# Attenuator_Proto.net
KiCad netlist of a schematic drawn in Altium Designer
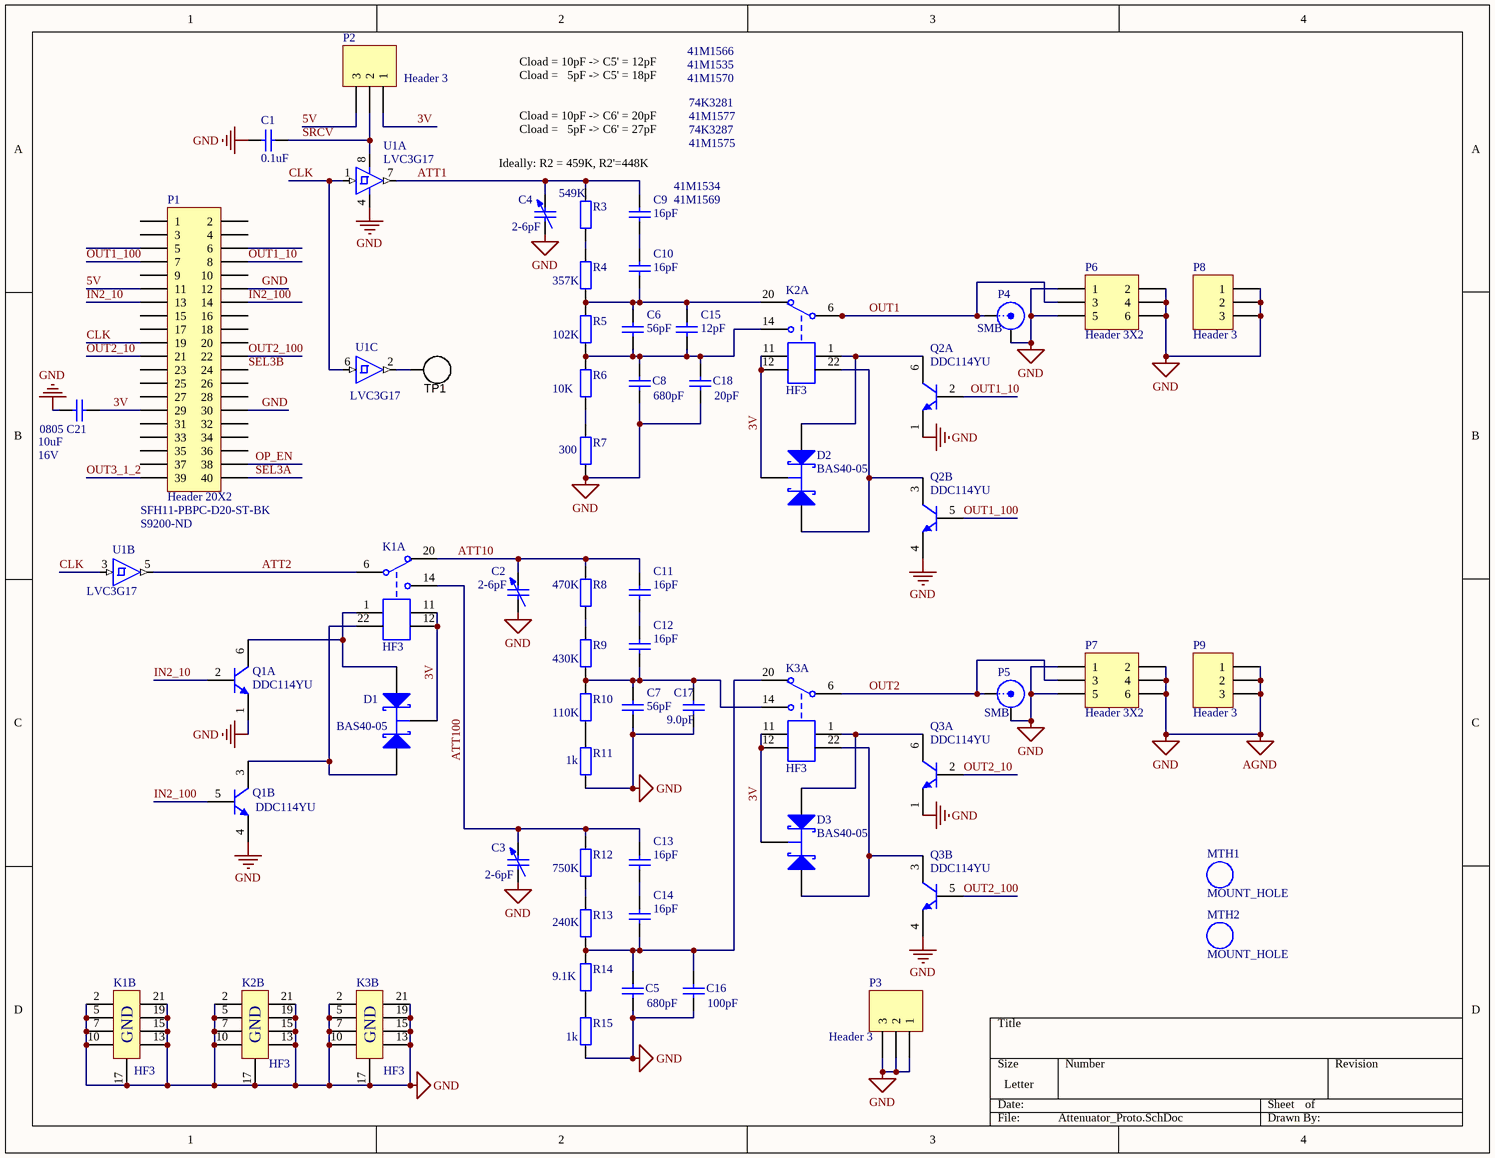
[diagram p0: Attenuator_Proto.SchDoc]

(export (version "E")
  (design (tool "Eeschema 10.0.6"))
  (components
    (comp (ref "C1")
      (value "0.1uF")
      (footprint "C0805")
      (description "Capacitor")
      (fields (field (name "Comment") "Cap") (field (name "PUBLISHER") "Altium Limited"))
      (libsource (lib "Miscellaneous Devices") (part "Cap"))
    )
    (comp (ref "C2")
      (value "2-6pF")
      (footprint "CAPC3225N")
      (description "Variable or Adjustable Capacitor")
      (fields (field (name "Comment") "Cap Var") (field (name "PUBLISHER") "Altium Limited"))
      (libsource (lib "Miscellaneous Devices") (part "Cap Var"))
    )
    (comp (ref "C3")
      (value "2-6pF")
      (footprint "CAPC3225N")
      (description "Variable or Adjustable Capacitor")
      (fields (field (name "Comment") "Cap Var") (field (name "PUBLISHER") "Altium Limited"))
      (libsource (lib "Miscellaneous Devices") (part "Cap Var"))
    )
    (comp (ref "C4")
      (value "2-6pF")
      (footprint "CAPC3225N")
      (description "Variable or Adjustable Capacitor")
      (fields (field (name "Comment") "Cap Var") (field (name "PUBLISHER") "Altium Limited"))
      (libsource (lib "Miscellaneous Devices") (part "Cap Var"))
    )
    (comp (ref "C5")
      (value "680pF")
      (footprint "c0805")
      (description "Capacitor")
      (fields (field (name "Comment") "Cap") (field (name "PUBLISHER") "Altium Limited"))
      (libsource (lib "Miscellaneous Devices") (part "Cap"))
    )
    (comp (ref "C6")
      (value "56pF")
      (footprint "c0805")
      (description "Capacitor")
      (fields (field (name "Comment") "Cap") (field (name "PUBLISHER") "Altium Limited"))
      (libsource (lib "Miscellaneous Devices") (part "Cap"))
    )
    (comp (ref "C7")
      (value "56pF")
      (footprint "c0805")
      (description "Capacitor")
      (fields (field (name "Comment") "Cap") (field (name "PUBLISHER") "Altium Limited"))
      (libsource (lib "Miscellaneous Devices") (part "Cap"))
    )
    (comp (ref "C8")
      (value "680pF")
      (footprint "c0805")
      (description "Capacitor")
      (fields (field (name "Comment") "Cap") (field (name "PUBLISHER") "Altium Limited"))
      (libsource (lib "Miscellaneous Devices") (part "Cap"))
    )
    (comp (ref "C9")
      (value "16pF")
      (footprint "c0805")
      (description "Capacitor")
      (fields
        (field (name "SUPPLIER PART NUMBER 1") "41M1569")
        (field (name "SUPPLIER PART NUMBER 2") "41M1534")
        (field (name "Comment") "Cap")
        (field (name "PUBLISHER") "Altium Limited")
      )
      (libsource (lib "Miscellaneous Devices") (part "Cap"))
    )
    (comp (ref "C10")
      (value "16pF")
      (footprint "c0805")
      (description "Capacitor")
      (fields (field (name "Comment") "Cap") (field (name "PUBLISHER") "Altium Limited"))
      (libsource (lib "Miscellaneous Devices") (part "Cap"))
    )
    (comp (ref "C11")
      (value "16pF")
      (footprint "c0805")
      (description "Capacitor")
      (fields (field (name "Comment") "Cap") (field (name "PUBLISHER") "Altium Limited"))
      (libsource (lib "Miscellaneous Devices") (part "Cap"))
    )
    (comp (ref "C12")
      (value "16pF")
      (footprint "c0805")
      (description "Capacitor")
      (fields (field (name "Comment") "Cap") (field (name "PUBLISHER") "Altium Limited"))
      (libsource (lib "Miscellaneous Devices") (part "Cap"))
    )
    (comp (ref "C13")
      (value "16pF")
      (footprint "c0805")
      (description "Capacitor")
      (fields (field (name "Comment") "Cap") (field (name "PUBLISHER") "Altium Limited"))
      (libsource (lib "Miscellaneous Devices") (part "Cap"))
    )
    (comp (ref "C14")
      (value "16pF")
      (footprint "c0805")
      (description "Capacitor")
      (fields (field (name "Comment") "Cap") (field (name "PUBLISHER") "Altium Limited"))
      (libsource (lib "Miscellaneous Devices") (part "Cap"))
    )
    (comp (ref "C15")
      (value "12pF")
      (footprint "c0805")
      (description "Capacitor")
      (fields
        (field (name "SUPPLIER PART NUMBER 2") "41M1570")
        (field (name "SUPPLIER PART NUMBER 1") "41M1535")
        (field (name "SUPPLIER PART NUMBER 3") "41M1566")
        (field (name "Comment") "Cap")
        (field (name "PUBLISHER") "Altium Limited")
      )
      (libsource (lib "Miscellaneous Devices") (part "Cap"))
    )
    (comp (ref "C16")
      (value "100pF")
      (footprint "c0805")
      (description "Capacitor")
      (fields (field (name "Comment") "Cap") (field (name "PUBLISHER") "Altium Limited"))
      (libsource (lib "Miscellaneous Devices") (part "Cap"))
    )
    (comp (ref "C17")
      (value "9.0pF")
      (footprint "c0805")
      (description "Capacitor")
      (fields (field (name "Comment") "Cap") (field (name "PUBLISHER") "Altium Limited"))
      (libsource (lib "Miscellaneous Devices") (part "Cap"))
    )
    (comp (ref "C18")
      (value "20pF")
      (footprint "c0805")
      (description "Capacitor")
      (fields
        (field (name "SUPPLIER PART NUMBER 1") "41M1575")
        (field (name "SUPPLIER PART NUMBER 2") "74K3287")
        (field (name "SUPPLIER PART NUMBER 3") "41M1577")
        (field (name "SUPPLIER PART NUMBER 4") "74K3281")
        (field (name "Comment") "Cap")
        (field (name "PUBLISHER") "Altium Limited")
      )
      (libsource (lib "Miscellaneous Devices") (part "Cap"))
    )
    (comp (ref "C21")
      (value "10uF")
      (footprint "CAPC2512L")
      (description "Capacitor (Semiconductor SIM Model)")
      (fields
        (field (name "PACKAGEREFERENCE") "0805")
        (field (name "VOLTAGE") "16V")
        (field (name "MANUFACTURER") "Murata")
        (field (name "PARTNUMBER") "GRM21BF51C106ZE15L")
        (field (name "PUBLISHER") "Altium Limited")
      )
      (libsource (lib "Miscellaneous Devices") (part "Cap Semi"))
    )
    (comp (ref "D1")
      (value "BAS40-05")
      (footprint "SOT-23")
      (description "Silicon AF Schottky Diode for High-Speed Switching")
      (fields (field (name "PUBLISHER") "Altium Limited"))
      (libsource (lib "Infineon Discrete Diode") (part "BAS40-05"))
    )
    (comp (ref "D2")
      (value "BAS40-05")
      (footprint "SOT-23")
      (description "Silicon AF Schottky Diode for High-Speed Switching")
      (fields (field (name "PUBLISHER") "Altium Limited"))
      (libsource (lib "Infineon Discrete Diode") (part "BAS40-05"))
    )
    (comp (ref "D3")
      (value "BAS40-05")
      (footprint "SOT-23")
      (description "Silicon AF Schottky Diode for High-Speed Switching")
      (fields (field (name "PUBLISHER") "Altium Limited"))
      (libsource (lib "Infineon Discrete Diode") (part "BAS40-05"))
    )
    (comp (ref "K1")
      (value "HF3_2coils_latching")
      (footprint "HF3-75_Ohm")
      (description "HF3 Relay, Latching type, 2 coils")
      (fields (field (name "MANUFACTURER") "Tyco Electronics") (field (name "PARTNUMBER") "HF3"))
      (libsource (lib "Chudik") (part "HF3_2coils_latching"))
    )
    (comp (ref "K2")
      (value "HF3_2coils_latching")
      (footprint "HF3-75_Ohm")
      (description "HF3 Relay, Latching type, 2 coils")
      (fields (field (name "MANUFACTURER") "Tyco Electronics") (field (name "PARTNUMBER") "HF3"))
      (libsource (lib "Chudik") (part "HF3_2coils_latching"))
    )
    (comp (ref "K3")
      (value "HF3_2coils_latching")
      (footprint "HF3-75_Ohm")
      (description "HF3 Relay, Latching type, 2 coils")
      (fields (field (name "MANUFACTURER") "Tyco Electronics") (field (name "PARTNUMBER") "HF3"))
      (libsource (lib "") (part "HF3_2coils_latching_1"))
    )
    (comp (ref "MTH1")
      (value "MOUNT_HOLE")
      (footprint "MTHOLE_UEG_EU_BE")
      (libsource (lib "CONTROLLER_BOARD") (part "MOUNT_HOLE"))
    )
    (comp (ref "MTH2")
      (value "MOUNT_HOLE")
      (footprint "MTHOLE_UEG_EU_BE")
      (libsource (lib "CONTROLLER_BOARD") (part "MOUNT_HOLE"))
    )
    (comp (ref "P1")
      (value "Header 20X2")
      (footprint "HDR2X20")
      (description "Header, 20-Pin, Dual row")
      (fields
        (field (name "PARTNUMBER") "SFH11-PBPC-D20-ST-BK")
        (field (name "SUPPLIER PART NUMBER 1") "S9200-ND")
        (field (name "PUBLISHER") "Altium Limited")
      )
      (libsource (lib "Miscellaneous Connectors") (part "Header 20X2"))
    )
    (comp (ref "P2")
      (value "Header 3")
      (footprint "HDR1X3")
      (description "Header, 3-Pin")
      (fields (field (name "PUBLISHER") "Altium Limited"))
      (libsource (lib "") (part "Header 3_1"))
    )
    (comp (ref "P3")
      (value "Header 3")
      (footprint "HDR1X3")
      (description "Header, 3-Pin")
      (fields (field (name "PUBLISHER") "Altium Limited"))
      (libsource (lib "") (part "Header 3_2"))
    )
    (comp (ref "P4")
      (value "SMB")
      (footprint "SMB_V-RJ45")
      (description "SMB Straight Connector")
      (fields (field (name "PUBLISHER") "Altium Limited"))
      (libsource (lib "Miscellaneous Connectors") (part "SMB"))
    )
    (comp (ref "P5")
      (value "SMB")
      (footprint "SMB_V-RJ45")
      (description "SMB Straight Connector")
      (fields (field (name "PUBLISHER") "Altium Limited"))
      (libsource (lib "Miscellaneous Connectors") (part "SMB"))
    )
    (comp (ref "P6")
      (value "Header 3X2")
      (footprint "HDR2X3")
      (description "Header, 3-Pin, Dual row")
      (fields (field (name "PUBLISHER") "Altium Limited"))
      (libsource (lib "Miscellaneous Connectors") (part "Header 3X2"))
    )
    (comp (ref "P7")
      (value "Header 3X2")
      (footprint "HDR2X3")
      (description "Header, 3-Pin, Dual row")
      (fields (field (name "PUBLISHER") "Altium Limited"))
      (libsource (lib "Miscellaneous Connectors") (part "Header 3X2"))
    )
    (comp (ref "P8")
      (value "Header 3")
      (footprint "HDR1X3")
      (description "Header, 3-Pin")
      (fields (field (name "PUBLISHER") "Altium Limited"))
      (libsource (lib "Miscellaneous Connectors") (part "Header 3"))
    )
    (comp (ref "P9")
      (value "Header 3")
      (footprint "HDR1X3")
      (description "Header, 3-Pin")
      (fields (field (name "PUBLISHER") "Altium Limited"))
      (libsource (lib "Miscellaneous Connectors") (part "Header 3"))
    )
    (comp (ref "Q1")
      (value "DDCxxxxU")
      (footprint "SOT-363")
      (description "NPN PRE-BIASED SMALL SIGNAL DUAL SURFACE MOUNT TRANSISTOR")
      (fields (field (name "PARTNUMBER") "DDC114YU"))
      (libsource (lib "iXBT") (part "DDCxxxxU"))
    )
    (comp (ref "Q2")
      (value "DDCxxxxU")
      (footprint "SOT-363")
      (description "NPN PRE-BIASED SMALL SIGNAL DUAL SURFACE MOUNT TRANSISTOR")
      (fields (field (name "PARTNUMBER") "DDC114YU"))
      (libsource (lib "iXBT") (part "DDCxxxxU"))
    )
    (comp (ref "Q3")
      (value "DDCxxxxU")
      (footprint "SOT-363")
      (description "NPN PRE-BIASED SMALL SIGNAL DUAL SURFACE MOUNT TRANSISTOR")
      (fields (field (name "PARTNUMBER") "DDC114YU"))
      (libsource (lib "iXBT") (part "DDCxxxxU"))
    )
    (comp (ref "R3")
      (value "549K")
      (footprint "0805")
      (description "Resistor")
      (fields (field (name "Comment") "Res2") (field (name "PUBLISHER") "Altium Limited"))
      (libsource (lib "Miscellaneous Devices") (part "Res2"))
    )
    (comp (ref "R4")
      (value "357K")
      (footprint "0805")
      (description "Resistor")
      (fields (field (name "Comment") "Res2") (field (name "PUBLISHER") "Altium Limited"))
      (libsource (lib "Miscellaneous Devices") (part "Res2"))
    )
    (comp (ref "R5")
      (value "102K")
      (footprint "0805")
      (description "Resistor")
      (fields (field (name "Comment") "Res2") (field (name "PUBLISHER") "Altium Limited"))
      (libsource (lib "Miscellaneous Devices") (part "Res2"))
    )
    (comp (ref "R6")
      (value "10K")
      (footprint "0805")
      (description "Resistor")
      (fields (field (name "Comment") "Res2") (field (name "PUBLISHER") "Altium Limited"))
      (libsource (lib "Miscellaneous Devices") (part "Res2"))
    )
    (comp (ref "R7")
      (value "300")
      (footprint "0805")
      (description "Resistor")
      (fields (field (name "Comment") "Res2") (field (name "PUBLISHER") "Altium Limited"))
      (libsource (lib "Miscellaneous Devices") (part "Res2"))
    )
    (comp (ref "R8")
      (value "470K")
      (footprint "0805")
      (description "Resistor")
      (fields (field (name "Comment") "Res2") (field (name "PUBLISHER") "Altium Limited"))
      (libsource (lib "Miscellaneous Devices") (part "Res2"))
    )
    (comp (ref "R9")
      (value "430K")
      (footprint "0805")
      (description "Resistor")
      (fields (field (name "Comment") "Res2") (field (name "PUBLISHER") "Altium Limited"))
      (libsource (lib "Miscellaneous Devices") (part "Res2"))
    )
    (comp (ref "R10")
      (value "110K")
      (footprint "0805")
      (description "Resistor")
      (fields (field (name "Comment") "Res2") (field (name "PUBLISHER") "Altium Limited"))
      (libsource (lib "Miscellaneous Devices") (part "Res2"))
    )
    (comp (ref "R11")
      (value "1k")
      (footprint "0805")
      (description "Resistor")
      (fields (field (name "Comment") "Res2") (field (name "PUBLISHER") "Altium Limited"))
      (libsource (lib "Miscellaneous Devices") (part "Res2"))
    )
    (comp (ref "R12")
      (value "750K")
      (footprint "0805")
      (description "Resistor")
      (fields (field (name "Comment") "Res2") (field (name "PUBLISHER") "Altium Limited"))
      (libsource (lib "Miscellaneous Devices") (part "Res2"))
    )
    (comp (ref "R13")
      (value "240K")
      (footprint "0805")
      (description "Resistor")
      (fields (field (name "Comment") "Res2") (field (name "PUBLISHER") "Altium Limited"))
      (libsource (lib "Miscellaneous Devices") (part "Res2"))
    )
    (comp (ref "R14")
      (value "9.1K")
      (footprint "0805")
      (description "Resistor")
      (fields (field (name "Comment") "Res2") (field (name "PUBLISHER") "Altium Limited"))
      (libsource (lib "Miscellaneous Devices") (part "Res2"))
    )
    (comp (ref "R15")
      (value "1k")
      (footprint "0805")
      (description "Resistor")
      (fields (field (name "Comment") "Res2") (field (name "PUBLISHER") "Altium Limited"))
      (libsource (lib "Miscellaneous Devices") (part "Res2"))
    )
    (comp (ref "TP1")
      (value "TESTPOINT")
      (footprint "TESTPOINT")
      (description "TEST POINT.  No entry in BOM.")
      (libsource (lib "NSC MiscParts") (part "TESTPOINT"))
    )
    (comp (ref "U1")
      (value "LVC3G17")
      (footprint "sm8")
      (fields
        (field (name "MANUFACTURER") "Texas Instruments")
        (field (name "MANUFACTURER PART NUMBER") "SN74LVC3G17DCTR")
      )
      (libsource (lib "VIVENG_Library") (part "SN74LVC3G17DCTR"))
    )
  )
  (nets
    (net (code "1") (name "/3V") (class "Default")
      (node (ref "C21") (pin "1") (pinfunction "1_1") (pintype "passive"))
      (node (ref "D1") (pin "3") (pinfunction "K_3") (pintype "passive"))
      (node (ref "D2") (pin "3") (pinfunction "K_3") (pintype "passive"))
      (node (ref "D3") (pin "3") (pinfunction "K_3") (pintype "passive"))
      (node (ref "K1") (pin "11") (pinfunction "11_11") (pintype "passive"))
      (node (ref "K1") (pin "12") (pinfunction "12_12") (pintype "passive"))
      (node (ref "K2") (pin "11") (pinfunction "11_11") (pintype "passive"))
      (node (ref "K2") (pin "12") (pinfunction "12_12") (pintype "passive"))
      (node (ref "K3") (pin "11") (pinfunction "11_11") (pintype "passive"))
      (node (ref "K3") (pin "12") (pinfunction "12_12") (pintype "passive"))
      (node (ref "P1") (pin "29") (pinfunction "29_29") (pintype "passive"))
      (node (ref "P2") (pin "1") (pinfunction "1_1") (pintype "passive"))
    )
    (net (code "2") (name "/5V") (class "Default")
      (node (ref "P1") (pin "11") (pinfunction "11_11") (pintype "passive"))
      (node (ref "P2") (pin "3") (pinfunction "3_3") (pintype "passive"))
    )
    (net (code "3") (name "/ATT1") (class "Default")
      (node (ref "C4") (pin "2") (pinfunction "2_2") (pintype "passive"))
      (node (ref "C9") (pin "2") (pinfunction "2_2") (pintype "passive"))
      (node (ref "R3") (pin "2") (pinfunction "2_2") (pintype "passive"))
      (node (ref "U1") (pin "7") (pinfunction "1Y_7") (pintype "output"))
    )
    (net (code "4") (name "/ATT2") (class "Default")
      (node (ref "K1") (pin "6") (pinfunction "6_6") (pintype "passive"))
      (node (ref "U1") (pin "5") (pinfunction "2Y_5") (pintype "output"))
    )
    (net (code "5") (name "/ATT10") (class "Default")
      (node (ref "C11") (pin "2") (pinfunction "2_2") (pintype "passive"))
      (node (ref "C2") (pin "2") (pinfunction "2_2") (pintype "passive"))
      (node (ref "K1") (pin "20") (pinfunction "20_20") (pintype "passive"))
      (node (ref "R8") (pin "2") (pinfunction "2_2") (pintype "passive"))
    )
    (net (code "6") (name "/ATT100") (class "Default")
      (node (ref "C13") (pin "2") (pinfunction "2_2") (pintype "passive"))
      (node (ref "C3") (pin "2") (pinfunction "2_2") (pintype "passive"))
      (node (ref "K1") (pin "14") (pinfunction "14_14") (pintype "passive"))
      (node (ref "R12") (pin "2") (pinfunction "2_2") (pintype "passive"))
    )
    (net (code "7") (name "/CLK") (class "Default")
      (node (ref "P1") (pin "19") (pinfunction "19_19") (pintype "passive"))
      (node (ref "U1") (pin "1") (pinfunction "1A_1") (pintype "input"))
      (node (ref "U1") (pin "3") (pinfunction "2A_3") (pintype "input"))
      (node (ref "U1") (pin "6") (pinfunction "3A_6") (pintype "input"))
    )
    (net (code "8") (name "/IN2_10") (class "Default")
      (node (ref "P1") (pin "13") (pinfunction "13_13") (pintype "passive"))
      (node (ref "Q1") (pin "2") (pinfunction "B_2") (pintype "passive"))
    )
    (net (code "9") (name "/IN2_100") (class "Default")
      (node (ref "P1") (pin "14") (pinfunction "14_14") (pintype "passive"))
      (node (ref "Q1") (pin "5") (pinfunction "B_5") (pintype "passive"))
    )
    (net (code "10") (name "/OP_EN") (class "Default")
      (node (ref "P1") (pin "38") (pinfunction "38_38") (pintype "passive"))
    )
    (net (code "11") (name "/OUT1") (class "Default")
      (node (ref "K2") (pin "6") (pinfunction "6_6") (pintype "passive"))
      (node (ref "P4") (pin "1") (pinfunction "X_1") (pintype "passive"))
      (node (ref "P6") (pin "3") (pinfunction "3_3") (pintype "passive"))
    )
    (net (code "12") (name "/OUT1_10") (class "Default")
      (node (ref "P1") (pin "8") (pinfunction "8_8") (pintype "passive"))
      (node (ref "Q2") (pin "2") (pinfunction "B_2") (pintype "passive"))
    )
    (net (code "13") (name "/OUT1_100") (class "Default")
      (node (ref "P1") (pin "7") (pinfunction "7_7") (pintype "passive"))
      (node (ref "Q2") (pin "5") (pinfunction "B_5") (pintype "passive"))
    )
    (net (code "14") (name "/OUT2") (class "Default")
      (node (ref "K3") (pin "6") (pinfunction "6_6") (pintype "passive"))
      (node (ref "P5") (pin "1") (pinfunction "X_1") (pintype "passive"))
      (node (ref "P7") (pin "3") (pinfunction "3_3") (pintype "passive"))
    )
    (net (code "15") (name "/OUT2_10") (class "Default")
      (node (ref "P1") (pin "21") (pinfunction "21_21") (pintype "passive"))
      (node (ref "Q3") (pin "2") (pinfunction "B_2") (pintype "passive"))
    )
    (net (code "16") (name "/OUT2_100") (class "Default")
      (node (ref "P1") (pin "22") (pinfunction "22_22") (pintype "passive"))
      (node (ref "Q3") (pin "5") (pinfunction "B_5") (pintype "passive"))
    )
    (net (code "17") (name "/OUT3_1_2") (class "Default")
      (node (ref "P1") (pin "39") (pinfunction "39_39") (pintype "passive"))
    )
    (net (code "18") (name "/SEL3A") (class "Default")
      (node (ref "P1") (pin "40") (pinfunction "40_40") (pintype "passive"))
    )
    (net (code "19") (name "/SEL3B") (class "Default")
      (node (ref "P1") (pin "24") (pinfunction "24_24") (pintype "passive"))
    )
    (net (code "20") (name "/SRCV") (class "Default")
      (node (ref "C1") (pin "1") (pinfunction "1_1") (pintype "passive"))
      (node (ref "P2") (pin "2") (pinfunction "2_2") (pintype "passive"))
      (node (ref "U1") (pin "8") (pinfunction "VCC_8") (pintype "power_in"))
    )
    (net (code "21") (name "AGND") (class "Default")
      (node (ref "C1") (pin "2") (pinfunction "2_2") (pintype "passive"))
      (node (ref "C16") (pin "1") (pinfunction "1_1") (pintype "passive"))
      (node (ref "C17") (pin "1") (pinfunction "1_1") (pintype "passive"))
      (node (ref "C18") (pin "1") (pinfunction "1_1") (pintype "passive"))
      (node (ref "C2") (pin "1") (pinfunction "1_1") (pintype "passive"))
      (node (ref "C21") (pin "2") (pinfunction "2_2") (pintype "passive"))
      (node (ref "C3") (pin "1") (pinfunction "1_1") (pintype "passive"))
      (node (ref "C4") (pin "1") (pinfunction "1_1") (pintype "passive"))
      (node (ref "C5") (pin "1") (pinfunction "1_1") (pintype "passive"))
      (node (ref "C7") (pin "1") (pinfunction "1_1") (pintype "passive"))
      (node (ref "C8") (pin "1") (pinfunction "1_1") (pintype "passive"))
      (node (ref "K1") (pin "10") (pinfunction "GND_10") (pintype "power_in"))
      (node (ref "K1") (pin "13") (pinfunction "GND_13") (pintype "power_in"))
      (node (ref "K1") (pin "15") (pinfunction "GND_15") (pintype "power_in"))
      (node (ref "K1") (pin "17") (pinfunction "GND_17") (pintype "power_in"))
      (node (ref "K1") (pin "19") (pinfunction "GND_19") (pintype "power_in"))
      (node (ref "K1") (pin "2") (pinfunction "GND_2") (pintype "power_in"))
      (node (ref "K1") (pin "21") (pinfunction "GND_21") (pintype "power_in"))
      (node (ref "K1") (pin "5") (pinfunction "GND_5") (pintype "power_in"))
      (node (ref "K1") (pin "7") (pinfunction "GND_7") (pintype "power_in"))
      (node (ref "K2") (pin "10") (pinfunction "GND_10") (pintype "power_in"))
      (node (ref "K2") (pin "13") (pinfunction "GND_13") (pintype "power_in"))
      (node (ref "K2") (pin "15") (pinfunction "GND_15") (pintype "power_in"))
      (node (ref "K2") (pin "17") (pinfunction "GND_17") (pintype "power_in"))
      (node (ref "K2") (pin "19") (pinfunction "GND_19") (pintype "power_in"))
      (node (ref "K2") (pin "2") (pinfunction "GND_2") (pintype "power_in"))
      (node (ref "K2") (pin "21") (pinfunction "GND_21") (pintype "power_in"))
      (node (ref "K2") (pin "5") (pinfunction "GND_5") (pintype "power_in"))
      (node (ref "K2") (pin "7") (pinfunction "GND_7") (pintype "power_in"))
      (node (ref "K3") (pin "10") (pinfunction "GND_10") (pintype "power_in"))
      (node (ref "K3") (pin "13") (pinfunction "GND_13") (pintype "power_in"))
      (node (ref "K3") (pin "15") (pinfunction "GND_15") (pintype "power_in"))
      (node (ref "K3") (pin "17") (pinfunction "GND_17") (pintype "power_in"))
      (node (ref "K3") (pin "19") (pinfunction "GND_19") (pintype "power_in"))
      (node (ref "K3") (pin "2") (pinfunction "GND_2") (pintype "power_in"))
      (node (ref "K3") (pin "21") (pinfunction "GND_21") (pintype "power_in"))
      (node (ref "K3") (pin "5") (pinfunction "GND_5") (pintype "power_in"))
      (node (ref "K3") (pin "7") (pinfunction "GND_7") (pintype "power_in"))
      (node (ref "P1") (pin "12") (pinfunction "12_12") (pintype "passive"))
      (node (ref "P1") (pin "30") (pinfunction "30_30") (pintype "passive"))
      (node (ref "P3") (pin "1") (pinfunction "1_1") (pintype "passive"))
      (node (ref "P3") (pin "2") (pinfunction "2_2") (pintype "passive"))
      (node (ref "P3") (pin "3") (pinfunction "3_3") (pintype "passive"))
      (node (ref "P4") (pin "2") (pinfunction "Y_2") (pintype "passive"))
      (node (ref "P5") (pin "2") (pinfunction "Y_2") (pintype "passive"))
      (node (ref "P6") (pin "1") (pinfunction "1_1") (pintype "passive"))
      (node (ref "P6") (pin "2") (pinfunction "2_2") (pintype "passive"))
      (node (ref "P6") (pin "4") (pinfunction "4_4") (pintype "passive"))
      (node (ref "P6") (pin "5") (pinfunction "5_5") (pintype "passive"))
      (node (ref "P6") (pin "6") (pinfunction "6_6") (pintype "passive"))
      (node (ref "P7") (pin "1") (pinfunction "1_1") (pintype "passive"))
      (node (ref "P7") (pin "2") (pinfunction "2_2") (pintype "passive"))
      (node (ref "P7") (pin "4") (pinfunction "4_4") (pintype "passive"))
      (node (ref "P7") (pin "5") (pinfunction "5_5") (pintype "passive"))
      (node (ref "P7") (pin "6") (pinfunction "6_6") (pintype "passive"))
      (node (ref "P8") (pin "1") (pinfunction "1_1") (pintype "passive"))
      (node (ref "P8") (pin "2") (pinfunction "2_2") (pintype "passive"))
      (node (ref "P8") (pin "3") (pinfunction "3_3") (pintype "passive"))
      (node (ref "P9") (pin "1") (pinfunction "1_1") (pintype "passive"))
      (node (ref "P9") (pin "2") (pinfunction "2_2") (pintype "passive"))
      (node (ref "P9") (pin "3") (pinfunction "3_3") (pintype "passive"))
      (node (ref "Q1") (pin "1") (pinfunction "E_1") (pintype "passive"))
      (node (ref "Q1") (pin "4") (pinfunction "E_4") (pintype "passive"))
      (node (ref "Q2") (pin "1") (pinfunction "E_1") (pintype "passive"))
      (node (ref "Q2") (pin "4") (pinfunction "E_4") (pintype "passive"))
      (node (ref "Q3") (pin "1") (pinfunction "E_1") (pintype "passive"))
      (node (ref "Q3") (pin "4") (pinfunction "E_4") (pintype "passive"))
      (node (ref "R11") (pin "1") (pinfunction "1_1") (pintype "passive"))
      (node (ref "R15") (pin "1") (pinfunction "1_1") (pintype "passive"))
      (node (ref "R7") (pin "1") (pinfunction "1_1") (pintype "passive"))
      (node (ref "U1") (pin "4") (pinfunction "GND_4") (pintype "power_in"))
    )
    (net (code "22") (name "Net-(C10-Pad1)") (class "Default")
      (node (ref "C10") (pin "1") (pinfunction "1_1") (pintype "passive"))
      (node (ref "C15") (pin "2") (pinfunction "2_2") (pintype "passive"))
      (node (ref "C6") (pin "2") (pinfunction "2_2") (pintype "passive"))
      (node (ref "K2") (pin "20") (pinfunction "20_20") (pintype "passive"))
      (node (ref "R4") (pin "1") (pinfunction "1_1") (pintype "passive"))
      (node (ref "R5") (pin "2") (pinfunction "2_2") (pintype "passive"))
    )
    (net (code "23") (name "Net-(C10-Pad2)") (class "Default")
      (node (ref "C10") (pin "2") (pinfunction "2_2") (pintype "passive"))
      (node (ref "C9") (pin "1") (pinfunction "1_1") (pintype "passive"))
    )
    (net (code "24") (name "Net-(C11-Pad1)") (class "Default")
      (node (ref "C11") (pin "1") (pinfunction "1_1") (pintype "passive"))
      (node (ref "C12") (pin "2") (pinfunction "2_2") (pintype "passive"))
    )
    (net (code "25") (name "Net-(C12-Pad1)") (class "Default")
      (node (ref "C12") (pin "1") (pinfunction "1_1") (pintype "passive"))
      (node (ref "C17") (pin "2") (pinfunction "2_2") (pintype "passive"))
      (node (ref "C7") (pin "2") (pinfunction "2_2") (pintype "passive"))
      (node (ref "K3") (pin "14") (pinfunction "14_14") (pintype "passive"))
      (node (ref "R10") (pin "2") (pinfunction "2_2") (pintype "passive"))
      (node (ref "R9") (pin "1") (pinfunction "1_1") (pintype "passive"))
    )
    (net (code "26") (name "Net-(C13-Pad1)") (class "Default")
      (node (ref "C13") (pin "1") (pinfunction "1_1") (pintype "passive"))
      (node (ref "C14") (pin "2") (pinfunction "2_2") (pintype "passive"))
    )
    (net (code "27") (name "Net-(C14-Pad1)") (class "Default")
      (node (ref "C14") (pin "1") (pinfunction "1_1") (pintype "passive"))
      (node (ref "C16") (pin "2") (pinfunction "2_2") (pintype "passive"))
      (node (ref "C5") (pin "2") (pinfunction "2_2") (pintype "passive"))
      (node (ref "K3") (pin "20") (pinfunction "20_20") (pintype "passive"))
      (node (ref "R13") (pin "1") (pinfunction "1_1") (pintype "passive"))
      (node (ref "R14") (pin "2") (pinfunction "2_2") (pintype "passive"))
    )
    (net (code "28") (name "Net-(C15-Pad1)") (class "Default")
      (node (ref "C15") (pin "1") (pinfunction "1_1") (pintype "passive"))
      (node (ref "C18") (pin "2") (pinfunction "2_2") (pintype "passive"))
      (node (ref "C6") (pin "1") (pinfunction "1_1") (pintype "passive"))
      (node (ref "C8") (pin "2") (pinfunction "2_2") (pintype "passive"))
      (node (ref "K2") (pin "14") (pinfunction "14_14") (pintype "passive"))
      (node (ref "R5") (pin "1") (pinfunction "1_1") (pintype "passive"))
      (node (ref "R6") (pin "2") (pinfunction "2_2") (pintype "passive"))
    )
    (net (code "29") (name "Net-(D1-A1)") (class "Default")
      (node (ref "D1") (pin "1") (pinfunction "A1_1") (pintype "passive"))
      (node (ref "K1") (pin "1") (pinfunction "1_1") (pintype "passive"))
      (node (ref "Q1") (pin "6") (pinfunction "C_6") (pintype "passive"))
    )
    (net (code "30") (name "Net-(D1-A2)") (class "Default")
      (node (ref "D1") (pin "2") (pinfunction "A2_2") (pintype "passive"))
      (node (ref "K1") (pin "22") (pinfunction "22_22") (pintype "passive"))
      (node (ref "Q1") (pin "3") (pinfunction "C_3") (pintype "passive"))
    )
    (net (code "31") (name "Net-(D2-A1)") (class "Default")
      (node (ref "D2") (pin "1") (pinfunction "A1_1") (pintype "passive"))
      (node (ref "K2") (pin "1") (pinfunction "1_1") (pintype "passive"))
      (node (ref "Q2") (pin "6") (pinfunction "C_6") (pintype "passive"))
    )
    (net (code "32") (name "Net-(D2-A2)") (class "Default")
      (node (ref "D2") (pin "2") (pinfunction "A2_2") (pintype "passive"))
      (node (ref "K2") (pin "22") (pinfunction "22_22") (pintype "passive"))
      (node (ref "Q2") (pin "3") (pinfunction "C_3") (pintype "passive"))
    )
    (net (code "33") (name "Net-(D3-A1)") (class "Default")
      (node (ref "D3") (pin "1") (pinfunction "A1_1") (pintype "passive"))
      (node (ref "K3") (pin "1") (pinfunction "1_1") (pintype "passive"))
      (node (ref "Q3") (pin "6") (pinfunction "C_6") (pintype "passive"))
    )
    (net (code "34") (name "Net-(D3-A2)") (class "Default")
      (node (ref "D3") (pin "2") (pinfunction "A2_2") (pintype "passive"))
      (node (ref "K3") (pin "22") (pinfunction "22_22") (pintype "passive"))
      (node (ref "Q3") (pin "3") (pinfunction "C_3") (pintype "passive"))
    )
    (net (code "35") (name "Net-(R3-Pad1)") (class "Default")
      (node (ref "R3") (pin "1") (pinfunction "1_1") (pintype "passive"))
      (node (ref "R4") (pin "2") (pinfunction "2_2") (pintype "passive"))
    )
    (net (code "36") (name "Net-(R6-Pad1)") (class "Default")
      (node (ref "R6") (pin "1") (pinfunction "1_1") (pintype "passive"))
      (node (ref "R7") (pin "2") (pinfunction "2_2") (pintype "passive"))
    )
    (net (code "37") (name "Net-(R8-Pad1)") (class "Default")
      (node (ref "R8") (pin "1") (pinfunction "1_1") (pintype "passive"))
      (node (ref "R9") (pin "2") (pinfunction "2_2") (pintype "passive"))
    )
    (net (code "38") (name "Net-(R10-Pad1)") (class "Default")
      (node (ref "R10") (pin "1") (pinfunction "1_1") (pintype "passive"))
      (node (ref "R11") (pin "2") (pinfunction "2_2") (pintype "passive"))
    )
    (net (code "39") (name "Net-(R12-Pad1)") (class "Default")
      (node (ref "R12") (pin "1") (pinfunction "1_1") (pintype "passive"))
      (node (ref "R13") (pin "2") (pinfunction "2_2") (pintype "passive"))
    )
    (net (code "40") (name "Net-(R14-Pad1)") (class "Default")
      (node (ref "R14") (pin "1") (pinfunction "1_1") (pintype "passive"))
      (node (ref "R15") (pin "2") (pinfunction "2_2") (pintype "passive"))
    )
    (net (code "41") (name "Net-(U1C-3Y)") (class "Default")
      (node (ref "TP1") (pin "1") (pintype "passive"))
      (node (ref "U1") (pin "2") (pinfunction "3Y_2") (pintype "output"))
    )
    (net (code "42") (name "unconnected-(P1-Pad1)") (class "Default")
      (node (ref "P1") (pin "1") (pinfunction "1_1") (pintype "passive"))
    )
    (net (code "43") (name "unconnected-(P1-Pad2)") (class "Default")
      (node (ref "P1") (pin "2") (pinfunction "2_2") (pintype "passive"))
    )
    (net (code "44") (name "unconnected-(P1-Pad3)") (class "Default")
      (node (ref "P1") (pin "3") (pinfunction "3_3") (pintype "passive"))
    )
    (net (code "45") (name "unconnected-(P1-Pad4)") (class "Default")
      (node (ref "P1") (pin "4") (pinfunction "4_4") (pintype "passive"))
    )
    (net (code "46") (name "unconnected-(P1-Pad5)") (class "Default")
      (node (ref "P1") (pin "5") (pinfunction "5_5") (pintype "passive"))
    )
    (net (code "47") (name "unconnected-(P1-Pad6)") (class "Default")
      (node (ref "P1") (pin "6") (pinfunction "6_6") (pintype "passive"))
    )
    (net (code "48") (name "unconnected-(P1-Pad9)") (class "Default")
      (node (ref "P1") (pin "9") (pinfunction "9_9") (pintype "passive"))
    )
    (net (code "49") (name "unconnected-(P1-Pad10)") (class "Default")
      (node (ref "P1") (pin "10") (pinfunction "10_10") (pintype "passive"))
    )
    (net (code "50") (name "unconnected-(P1-Pad15)") (class "Default")
      (node (ref "P1") (pin "15") (pinfunction "15_15") (pintype "passive"))
    )
    (net (code "51") (name "unconnected-(P1-Pad16)") (class "Default")
      (node (ref "P1") (pin "16") (pinfunction "16_16") (pintype "passive"))
    )
    (net (code "52") (name "unconnected-(P1-Pad17)") (class "Default")
      (node (ref "P1") (pin "17") (pinfunction "17_17") (pintype "passive"))
    )
    (net (code "53") (name "unconnected-(P1-Pad18)") (class "Default")
      (node (ref "P1") (pin "18") (pinfunction "18_18") (pintype "passive"))
    )
    (net (code "54") (name "unconnected-(P1-Pad20)") (class "Default")
      (node (ref "P1") (pin "20") (pinfunction "20_20") (pintype "passive"))
    )
    (net (code "55") (name "unconnected-(P1-Pad23)") (class "Default")
      (node (ref "P1") (pin "23") (pinfunction "23_23") (pintype "passive"))
    )
    (net (code "56") (name "unconnected-(P1-Pad25)") (class "Default")
      (node (ref "P1") (pin "25") (pinfunction "25_25") (pintype "passive"))
    )
    (net (code "57") (name "unconnected-(P1-Pad26)") (class "Default")
      (node (ref "P1") (pin "26") (pinfunction "26_26") (pintype "passive"))
    )
    (net (code "58") (name "unconnected-(P1-Pad27)") (class "Default")
      (node (ref "P1") (pin "27") (pinfunction "27_27") (pintype "passive"))
    )
    (net (code "59") (name "unconnected-(P1-Pad28)") (class "Default")
      (node (ref "P1") (pin "28") (pinfunction "28_28") (pintype "passive"))
    )
    (net (code "60") (name "unconnected-(P1-Pad31)") (class "Default")
      (node (ref "P1") (pin "31") (pinfunction "31_31") (pintype "passive"))
    )
    (net (code "61") (name "unconnected-(P1-Pad32)") (class "Default")
      (node (ref "P1") (pin "32") (pinfunction "32_32") (pintype "passive"))
    )
    (net (code "62") (name "unconnected-(P1-Pad33)") (class "Default")
      (node (ref "P1") (pin "33") (pinfunction "33_33") (pintype "passive"))
    )
    (net (code "63") (name "unconnected-(P1-Pad34)") (class "Default")
      (node (ref "P1") (pin "34") (pinfunction "34_34") (pintype "passive"))
    )
    (net (code "64") (name "unconnected-(P1-Pad35)") (class "Default")
      (node (ref "P1") (pin "35") (pinfunction "35_35") (pintype "passive"))
    )
    (net (code "65") (name "unconnected-(P1-Pad36)") (class "Default")
      (node (ref "P1") (pin "36") (pinfunction "36_36") (pintype "passive"))
    )
    (net (code "66") (name "unconnected-(P1-Pad37)") (class "Default")
      (node (ref "P1") (pin "37") (pinfunction "37_37") (pintype "passive"))
    )
  )
)
